# ul_rx.net
KiCad netlist of a schematic drawn in Altium Designer
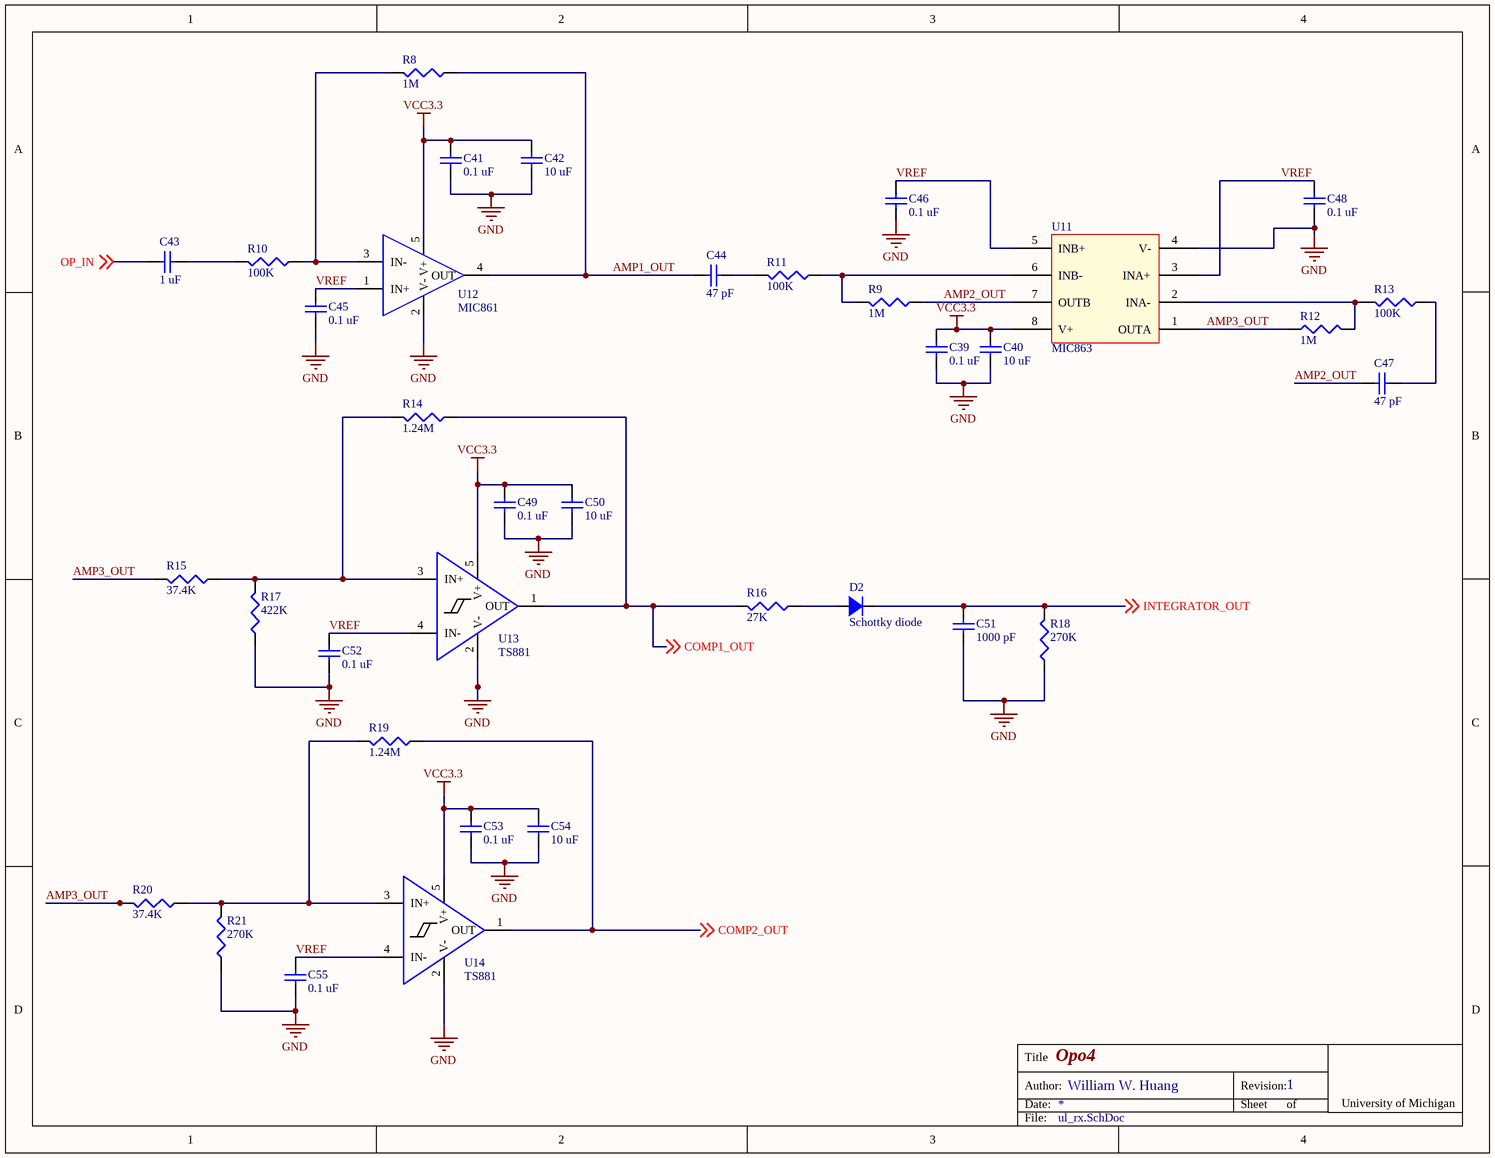
[diagram p0: ul_rx.SchDoc]

(export (version "E")
  (design (tool "Eeschema 10.0.6"))
  (components
    (comp (ref "C39")
      (value "0.1 uF")
      (footprint "0402")
      (description "Ceramic capacitor, 0.1u, 0402 package")
      (fields (field (name "TOLERANCE") "10%") (field (name "Comment") "Ceramic capacitor"))
      (libsource (lib "rlc") (part "C_0.1u_0402_ceramic"))
    )
    (comp (ref "C40")
      (value "10 uF")
      (footprint "0402")
      (description "Ceramic capacitor, 10 uF, 0402 package")
      (fields (field (name "TOLERANCE") "20%") (field (name "Comment") "Ceramic capacitor"))
      (libsource (lib "rlc") (part "C_10u_0402_ceramic"))
    )
    (comp (ref "C41")
      (value "0.1 uF")
      (footprint "0402")
      (description "Ceramic capacitor, 0.1u, 0402 package")
      (fields (field (name "TOLERANCE") "10%") (field (name "Comment") "Ceramic capacitor"))
      (libsource (lib "rlc") (part "C_0.1u_0402_ceramic"))
    )
    (comp (ref "C42")
      (value "10 uF")
      (footprint "0402")
      (description "Ceramic capacitor, 10 uF, 0402 package")
      (fields (field (name "TOLERANCE") "20%") (field (name "Comment") "Ceramic capacitor"))
      (libsource (lib "rlc") (part "C_10u_0402_ceramic"))
    )
    (comp (ref "C43")
      (value "1 uF")
      (footprint "0402")
      (description "Ceramic capacitor, 1 uF, 0402 package")
      (fields (field (name "TOLERANCE") "10%") (field (name "Comment") "Ceramic capacitor"))
      (libsource (lib "rlc") (part "C_1u_0402_ceramic"))
    )
    (comp (ref "C44")
      (value "47 pF")
      (footprint "0402")
      (description "Ceramic capacitor, 47 pF, 0402 package")
      (fields (field (name "TOLERANCE") "5%") (field (name "Comment") "Ceramic capacitor"))
      (libsource (lib "rlc") (part "C_47p_0402_ceramic"))
    )
    (comp (ref "C45")
      (value "0.1 uF")
      (footprint "0402")
      (description "Ceramic capacitor, 0.1u, 0402 package")
      (fields (field (name "TOLERANCE") "10%") (field (name "Comment") "Ceramic capacitor"))
      (libsource (lib "rlc") (part "C_0.1u_0402_ceramic"))
    )
    (comp (ref "C46")
      (value "0.1 uF")
      (footprint "0402")
      (description "Ceramic capacitor, 0.1u, 0402 package")
      (fields (field (name "TOLERANCE") "10%") (field (name "Comment") "Ceramic capacitor"))
      (libsource (lib "rlc") (part "C_0.1u_0402_ceramic"))
    )
    (comp (ref "C47")
      (value "47 pF")
      (footprint "0402")
      (description "Ceramic capacitor, 47 pF, 0402 package")
      (fields (field (name "TOLERANCE") "5%") (field (name "Comment") "Ceramic capacitor"))
      (libsource (lib "rlc") (part "C_47p_0402_ceramic"))
    )
    (comp (ref "C48")
      (value "0.1 uF")
      (footprint "0402")
      (description "Ceramic capacitor, 0.1u, 0402 package")
      (fields (field (name "TOLERANCE") "10%") (field (name "Comment") "Ceramic capacitor"))
      (libsource (lib "rlc") (part "C_0.1u_0402_ceramic"))
    )
    (comp (ref "C49")
      (value "0.1 uF")
      (footprint "0402")
      (description "Ceramic capacitor, 0.1u, 0402 package")
      (fields (field (name "TOLERANCE") "10%") (field (name "Comment") "Ceramic capacitor"))
      (libsource (lib "rlc") (part "C_0.1u_0402_ceramic"))
    )
    (comp (ref "C50")
      (value "10 uF")
      (footprint "0402")
      (description "Ceramic capacitor, 10 uF, 0402 package")
      (fields (field (name "TOLERANCE") "20%") (field (name "Comment") "Ceramic capacitor"))
      (libsource (lib "rlc") (part "C_10u_0402_ceramic"))
    )
    (comp (ref "C51")
      (value "1000 pF")
      (footprint "0402")
      (description "Ceramic capacitor, 1000 pF, 0402 package")
      (fields (field (name "TOLERANCE") "10%") (field (name "Comment") "Ceramic capacitor"))
      (libsource (lib "rlc") (part "C_1000p_0402_ceramic"))
    )
    (comp (ref "C52")
      (value "0.1 uF")
      (footprint "0402")
      (description "Ceramic capacitor, 0.1u, 0402 package")
      (fields (field (name "TOLERANCE") "10%") (field (name "Comment") "Ceramic capacitor"))
      (libsource (lib "rlc") (part "C_0.1u_0402_ceramic"))
    )
    (comp (ref "C53")
      (value "0.1 uF")
      (footprint "0402")
      (description "Ceramic capacitor, 0.1u, 0402 package")
      (fields (field (name "TOLERANCE") "10%") (field (name "Comment") "Ceramic capacitor"))
      (libsource (lib "rlc") (part "C_0.1u_0402_ceramic"))
    )
    (comp (ref "C54")
      (value "10 uF")
      (footprint "0402")
      (description "Ceramic capacitor, 10 uF, 0402 package")
      (fields (field (name "TOLERANCE") "20%") (field (name "Comment") "Ceramic capacitor"))
      (libsource (lib "rlc") (part "C_10u_0402_ceramic"))
    )
    (comp (ref "C55")
      (value "0.1 uF")
      (footprint "0402")
      (description "Ceramic capacitor, 0.1u, 0402 package")
      (fields (field (name "TOLERANCE") "10%") (field (name "Comment") "Ceramic capacitor"))
      (libsource (lib "rlc") (part "C_0.1u_0402_ceramic"))
    )
    (comp (ref "D2")
      (value "Schottky diode")
      (footprint "0603 - DIODE")
      (description "Schottky diode 30 V 0.1 A 0603")
      (libsource (lib "rlc") (part "D_SCHOTTKY_30V_0.1A_0603"))
    )
    (comp (ref "R8")
      (value "1M")
      (footprint "0402")
      (description "Chip resistor, 1M, 0402 package")
      (fields (field (name "TOLERANCE") "1%") (field (name "POWER") "1/16 W"))
      (libsource (lib "rlc") (part "R_1M_0402"))
    )
    (comp (ref "R9")
      (value "1M")
      (footprint "0402")
      (description "Chip resistor, 1M, 0402 package")
      (fields (field (name "TOLERANCE") "1%") (field (name "POWER") "1/16 W"))
      (libsource (lib "rlc") (part "R_1M_0402"))
    )
    (comp (ref "R10")
      (value "100K")
      (footprint "0402")
      (description "Chip resistor, 100K, 0402 package")
      (fields (field (name "TOLERANCE") "1%") (field (name "POWER") "1/16 W"))
      (libsource (lib "rlc") (part "R_100K_0402"))
    )
    (comp (ref "R11")
      (value "100K")
      (footprint "0402")
      (description "Chip resistor, 100K, 0402 package")
      (fields (field (name "TOLERANCE") "1%") (field (name "POWER") "1/16 W"))
      (libsource (lib "rlc") (part "R_100K_0402"))
    )
    (comp (ref "R12")
      (value "1M")
      (footprint "0402")
      (description "Chip resistor, 1M, 0402 package")
      (fields (field (name "TOLERANCE") "1%") (field (name "POWER") "1/16 W"))
      (libsource (lib "rlc") (part "R_1M_0402"))
    )
    (comp (ref "R13")
      (value "100K")
      (footprint "0402")
      (description "Chip resistor, 100K, 0402 package")
      (fields (field (name "TOLERANCE") "1%") (field (name "POWER") "1/16 W"))
      (libsource (lib "rlc") (part "R_100K_0402"))
    )
    (comp (ref "R14")
      (value "1.24M")
      (footprint "0402")
      (description "Chip resistor, 1.24M, 0402 package")
      (fields (field (name "TOLERANCE") "1%") (field (name "POWER") "1/16 W"))
      (libsource (lib "rlc") (part "R_1.24M_0402"))
    )
    (comp (ref "R15")
      (value "37.4K")
      (footprint "0402")
      (description "Chip resistor, 37.4K, 0402 package")
      (fields (field (name "TOLERANCE") "1%") (field (name "POWER") "1/16 W"))
      (libsource (lib "rlc") (part "R_37.4K_0402"))
    )
    (comp (ref "R16")
      (value "27K")
      (footprint "0402")
      (description "Chip resistor, 27K, 0402 package")
      (fields (field (name "TOLERANCE") "1%") (field (name "POWER") "1/16 W"))
      (libsource (lib "rlc") (part "R_27K_0402"))
    )
    (comp (ref "R17")
      (value "422K")
      (footprint "0402")
      (description "Chip resistor, 422K, 0402 package")
      (fields (field (name "TOLERANCE") "1%") (field (name "POWER") "1/16 W"))
      (libsource (lib "rlc") (part "R_422K_0402"))
    )
    (comp (ref "R18")
      (value "270K")
      (footprint "0402")
      (description "Chip resistor, 270K, 0402 package")
      (fields (field (name "TOLERANCE") "1%") (field (name "POWER") "1/16 W"))
      (libsource (lib "rlc") (part "R_270K_0402"))
    )
    (comp (ref "R19")
      (value "1.24M")
      (footprint "0402")
      (description "Chip resistor, 1.24M, 0402 package")
      (fields (field (name "TOLERANCE") "1%") (field (name "POWER") "1/16 W"))
      (libsource (lib "rlc") (part "R_1.24M_0402"))
    )
    (comp (ref "R20")
      (value "37.4K")
      (footprint "0402")
      (description "Chip resistor, 37.4K, 0402 package")
      (fields (field (name "TOLERANCE") "1%") (field (name "POWER") "1/16 W"))
      (libsource (lib "rlc") (part "R_37.4K_0402"))
    )
    (comp (ref "R21")
      (value "270K")
      (footprint "0402")
      (description "Chip resistor, 270K, 0402 package")
      (fields (field (name "TOLERANCE") "1%") (field (name "POWER") "1/16 W"))
      (libsource (lib "rlc") (part "R_270K_0402"))
    )
    (comp (ref "U11")
      (value "MIC863")
      (footprint "TSOP65P280X145-8N")
      (description "Dual Ultra Low Power Op Amp in SOT23-8")
      (libsource (lib "opo_general") (part "MIC863"))
    )
    (comp (ref "U12")
      (value "MIC861")
      (footprint "SC70-5")
      (description "IC OPAMP 400KHZ 2.7V ULT LP SC70")
      (libsource (lib "opo_general") (part "MIC861"))
    )
    (comp (ref "U13")
      (value "TS881")
      (footprint "SC70-5")
      (description "Rail-to-rail 1.1 V nanopower comparator")
      (libsource (lib "opo_general") (part "TS881"))
    )
    (comp (ref "U14")
      (value "TS881")
      (footprint "SC70-5")
      (description "Rail-to-rail 1.1 V nanopower comparator")
      (libsource (lib "opo_general") (part "TS881"))
    )
  )
  (nets
    (net (code "1") (name "/AMP1_OUT") (class "Default")
      (node (ref "C44") (pin "1") (pintype "passive"))
      (node (ref "R8") (pin "2") (pintype "passive"))
      (node (ref "U12") (pin "4") (pinfunction "OUT_4") (pintype "passive"))
    )
    (net (code "2") (name "/AMP2_OUT") (class "Default")
      (node (ref "C47") (pin "1") (pintype "passive"))
      (node (ref "R9") (pin "2") (pintype "passive"))
      (node (ref "U11") (pin "7") (pinfunction "OUTB_7") (pintype "passive"))
    )
    (net (code "3") (name "/AMP3_OUT") (class "Default")
      (node (ref "R12") (pin "2") (pintype "passive"))
      (node (ref "R15") (pin "1") (pintype "passive"))
      (node (ref "R20") (pin "1") (pintype "passive"))
      (node (ref "U11") (pin "1") (pinfunction "OUTA_1") (pintype "passive"))
    )
    (net (code "4") (name "/VREF") (class "Default")
      (node (ref "C45") (pin "1") (pintype "passive"))
      (node (ref "C46") (pin "1") (pintype "passive"))
      (node (ref "C48") (pin "1") (pintype "passive"))
      (node (ref "C52") (pin "1") (pintype "passive"))
      (node (ref "C55") (pin "1") (pintype "passive"))
      (node (ref "U11") (pin "3") (pinfunction "INA+_3") (pintype "passive"))
      (node (ref "U11") (pin "5") (pinfunction "INB+_5") (pintype "passive"))
      (node (ref "U12") (pin "1") (pinfunction "IN+_1") (pintype "passive"))
      (node (ref "U13") (pin "4") (pinfunction "IN-_4") (pintype "passive"))
      (node (ref "U14") (pin "4") (pinfunction "IN-_4") (pintype "passive"))
    )
    (net (code "5") (name "COMP1_OUT") (class "Default")
      (node (ref "R14") (pin "2") (pintype "passive"))
      (node (ref "R16") (pin "1") (pintype "passive"))
      (node (ref "U13") (pin "1") (pinfunction "OUT_1") (pintype "passive"))
    )
    (net (code "6") (name "COMP2_OUT") (class "Default")
      (node (ref "R19") (pin "2") (pintype "passive"))
      (node (ref "U14") (pin "1") (pinfunction "OUT_1") (pintype "passive"))
    )
    (net (code "7") (name "GND") (class "Default")
      (node (ref "C39") (pin "2") (pintype "passive"))
      (node (ref "C40") (pin "2") (pintype "passive"))
      (node (ref "C41") (pin "2") (pintype "passive"))
      (node (ref "C42") (pin "2") (pintype "passive"))
      (node (ref "C45") (pin "2") (pintype "passive"))
      (node (ref "C46") (pin "2") (pintype "passive"))
      (node (ref "C48") (pin "2") (pintype "passive"))
      (node (ref "C49") (pin "2") (pintype "passive"))
      (node (ref "C50") (pin "2") (pintype "passive"))
      (node (ref "C51") (pin "2") (pintype "passive"))
      (node (ref "C52") (pin "2") (pintype "passive"))
      (node (ref "C53") (pin "2") (pintype "passive"))
      (node (ref "C54") (pin "2") (pintype "passive"))
      (node (ref "C55") (pin "2") (pintype "passive"))
      (node (ref "R17") (pin "2") (pintype "passive"))
      (node (ref "R18") (pin "2") (pintype "passive"))
      (node (ref "R21") (pin "2") (pintype "passive"))
      (node (ref "U11") (pin "4") (pinfunction "V-_4") (pintype "passive"))
      (node (ref "U12") (pin "2") (pinfunction "V-_2") (pintype "passive"))
      (node (ref "U13") (pin "2") (pinfunction "V-_2") (pintype "passive"))
      (node (ref "U14") (pin "2") (pinfunction "V-_2") (pintype "passive"))
    )
    (net (code "8") (name "INTEGRATOR_OUT") (class "Default")
      (node (ref "C51") (pin "1") (pintype "passive"))
      (node (ref "D2") (pin "2") (pintype "passive"))
      (node (ref "R18") (pin "1") (pintype "passive"))
    )
    (net (code "9") (name "Net-(C43-Pad2)") (class "Default")
      (node (ref "C43") (pin "2") (pintype "passive"))
      (node (ref "R10") (pin "1") (pintype "passive"))
    )
    (net (code "10") (name "Net-(C44-Pad2)") (class "Default")
      (node (ref "C44") (pin "2") (pintype "passive"))
      (node (ref "R11") (pin "1") (pintype "passive"))
    )
    (net (code "11") (name "Net-(C47-Pad2)") (class "Default")
      (node (ref "C47") (pin "2") (pintype "passive"))
      (node (ref "R13") (pin "2") (pintype "passive"))
    )
    (net (code "12") (name "Net-(D2-Pad1)") (class "Default")
      (node (ref "D2") (pin "1") (pintype "passive"))
      (node (ref "R16") (pin "2") (pintype "passive"))
    )
    (net (code "13") (name "Net-(U11-INA-)") (class "Default")
      (node (ref "R12") (pin "1") (pintype "passive"))
      (node (ref "R13") (pin "1") (pintype "passive"))
      (node (ref "U11") (pin "2") (pinfunction "INA-_2") (pintype "passive"))
    )
    (net (code "14") (name "Net-(U11-INB-)") (class "Default")
      (node (ref "R11") (pin "2") (pintype "passive"))
      (node (ref "R9") (pin "1") (pintype "passive"))
      (node (ref "U11") (pin "6") (pinfunction "INB-_6") (pintype "passive"))
    )
    (net (code "15") (name "Net-(U12-IN-)") (class "Default")
      (node (ref "R10") (pin "2") (pintype "passive"))
      (node (ref "R8") (pin "1") (pintype "passive"))
      (node (ref "U12") (pin "3") (pinfunction "IN-_3") (pintype "passive"))
    )
    (net (code "16") (name "Net-(U13-IN+)") (class "Default")
      (node (ref "R14") (pin "1") (pintype "passive"))
      (node (ref "R15") (pin "2") (pintype "passive"))
      (node (ref "R17") (pin "1") (pintype "passive"))
      (node (ref "U13") (pin "3") (pinfunction "IN+_3") (pintype "passive"))
    )
    (net (code "17") (name "Net-(U14-IN+)") (class "Default")
      (node (ref "R19") (pin "1") (pintype "passive"))
      (node (ref "R20") (pin "2") (pintype "passive"))
      (node (ref "R21") (pin "1") (pintype "passive"))
      (node (ref "U14") (pin "3") (pinfunction "IN+_3") (pintype "passive"))
    )
    (net (code "18") (name "OP_IN") (class "Default") (node (ref "C43") (pin "1") (pintype "passive")))
    (net (code "19") (name "VCC3.3") (class "Default")
      (node (ref "C39") (pin "1") (pintype "passive"))
      (node (ref "C40") (pin "1") (pintype "passive"))
      (node (ref "C41") (pin "1") (pintype "passive"))
      (node (ref "C42") (pin "1") (pintype "passive"))
      (node (ref "C49") (pin "1") (pintype "passive"))
      (node (ref "C50") (pin "1") (pintype "passive"))
      (node (ref "C53") (pin "1") (pintype "passive"))
      (node (ref "C54") (pin "1") (pintype "passive"))
      (node (ref "U11") (pin "8") (pinfunction "V+_8") (pintype "passive"))
      (node (ref "U12") (pin "5") (pinfunction "V+_5") (pintype "passive"))
      (node (ref "U13") (pin "5") (pinfunction "V+_5") (pintype "passive"))
      (node (ref "U14") (pin "5") (pinfunction "V+_5") (pintype "passive"))
    )
  )
)
